# MAIN_TX.net
KiCad netlist of a schematic drawn in Altium Designer
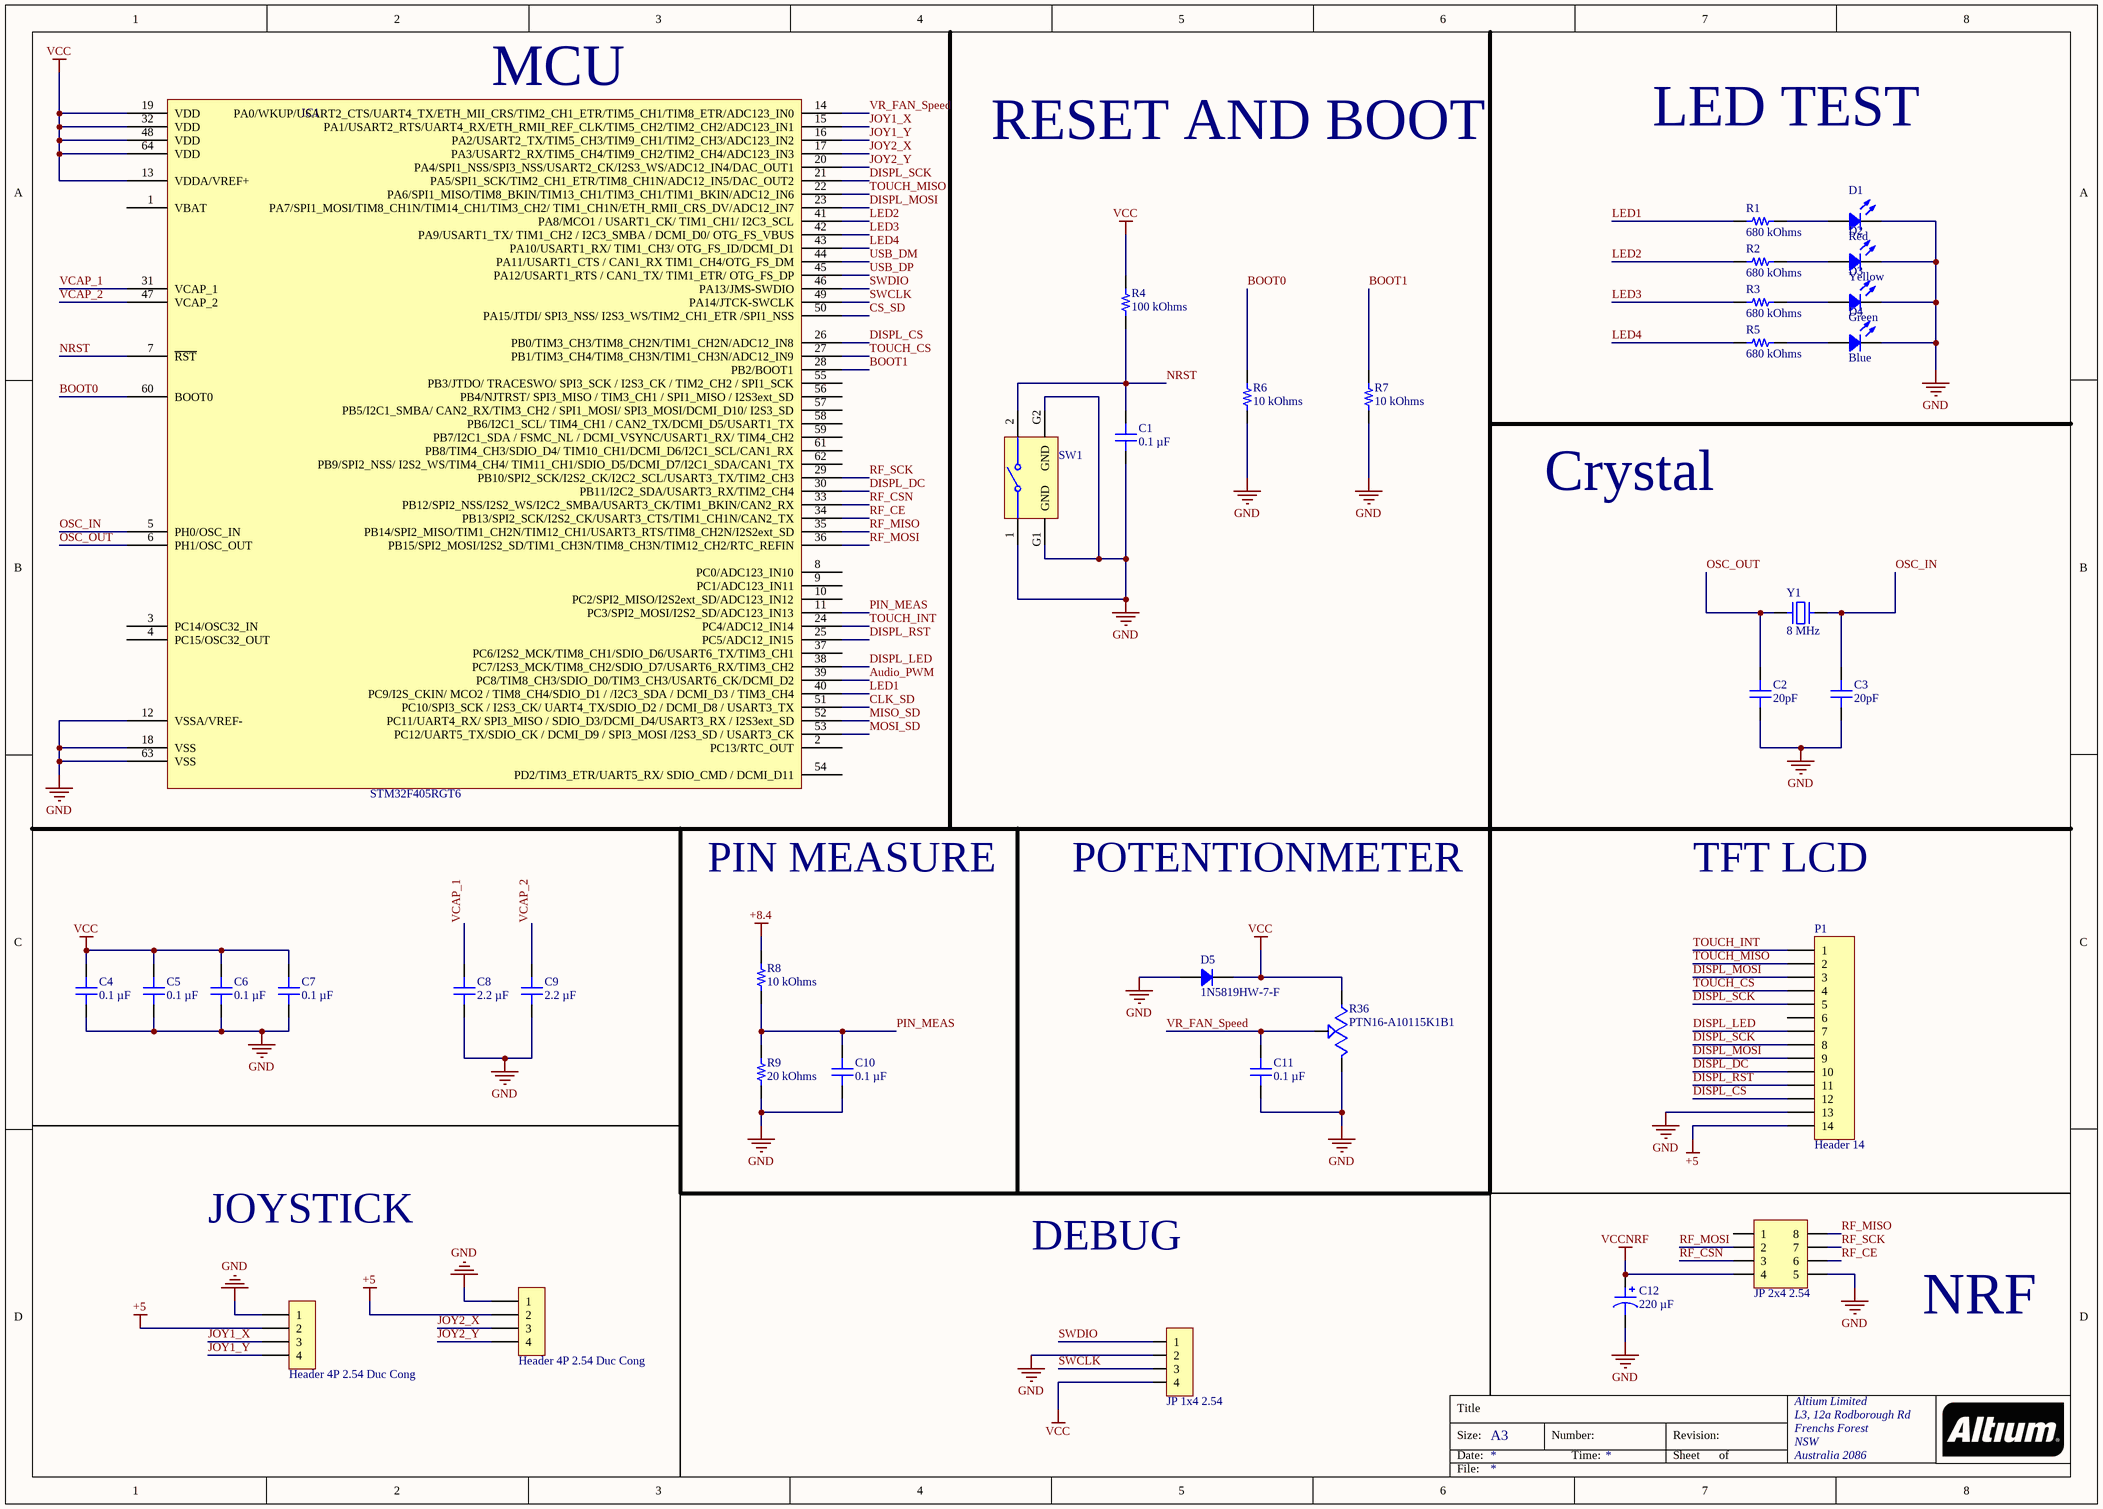
[diagram p0: MAIN_TX.SchDoc]

(export (version "E")
  (design (tool "Eeschema 10.0.6"))
  (components
    (comp (ref "C1")
      (value "0.1 µF")
      (footprint "CAP 0603_1608")
      (description "CAP CER 0.1UF 10V X7R 0603")
      (fields
        (field (name "PART NUMBER") "VJ0603Y104MXQCW1BC")
        (field (name "MANUFACTURER") "Vishay Vitramon")
      )
      (libsource (lib "Celestial Altium Library - altium_library") (part "Capacitor"))
    )
    (comp (ref "C2")
      (value "20pF")
      (footprint "CAP 0603_1608")
      (description "CAP CER 20PF 16V NP0 0603")
      (fields (field (name "PART NUMBER") "0603YA200JAT2A") (field (name "MANUFACTURER") "AVX Corporation"))
      (libsource (lib "Celestial Altium Library - altium_library") (part "Capacitor"))
    )
    (comp (ref "C3")
      (value "20pF")
      (footprint "CAP 0603_1608")
      (description "CAP CER 20PF 16V NP0 0603")
      (fields (field (name "PART NUMBER") "0603YA200JAT2A") (field (name "MANUFACTURER") "AVX Corporation"))
      (libsource (lib "Celestial Altium Library - altium_library") (part "Capacitor"))
    )
    (comp (ref "C4")
      (value "0.1 µF")
      (footprint "CAP 0603_1608")
      (description "CAP CER 0.1UF 10V X7R 0603")
      (fields
        (field (name "PART NUMBER") "VJ0603Y104MXQCW1BC")
        (field (name "MANUFACTURER") "Vishay Vitramon")
      )
      (libsource (lib "Celestial Altium Library - altium_library") (part "Capacitor"))
    )
    (comp (ref "C5")
      (value "0.1 µF")
      (footprint "CAP 0603_1608")
      (description "CAP CER 0.1UF 10V X7R 0603")
      (fields
        (field (name "PART NUMBER") "VJ0603Y104MXQCW1BC")
        (field (name "MANUFACTURER") "Vishay Vitramon")
      )
      (libsource (lib "Celestial Altium Library - altium_library") (part "Capacitor"))
    )
    (comp (ref "C6")
      (value "0.1 µF")
      (footprint "CAP 0603_1608")
      (description "CAP CER 0.1UF 10V X7R 0603")
      (fields
        (field (name "PART NUMBER") "VJ0603Y104MXQCW1BC")
        (field (name "MANUFACTURER") "Vishay Vitramon")
      )
      (libsource (lib "Celestial Altium Library - altium_library") (part "Capacitor"))
    )
    (comp (ref "C7")
      (value "0.1 µF")
      (footprint "CAP 0603_1608")
      (description "CAP CER 0.1UF 10V X7R 0603")
      (fields
        (field (name "PART NUMBER") "VJ0603Y104MXQCW1BC")
        (field (name "MANUFACTURER") "Vishay Vitramon")
      )
      (libsource (lib "Celestial Altium Library - altium_library") (part "Capacitor"))
    )
    (comp (ref "C8")
      (value "2.2 µF")
      (footprint "CAP 0603_1608")
      (description "CAP CER 2.2UF 10V X7R 0603")
      (fields (field (name "PART NUMBER") "LMK107B7225MA-TR") (field (name "MANUFACTURER") "Taiyo Yuden"))
      (libsource (lib "Celestial Altium Library - altium_library") (part "Capacitor"))
    )
    (comp (ref "C9")
      (value "2.2 µF")
      (footprint "CAP 0603_1608")
      (description "CAP CER 2.2UF 10V X7R 0603")
      (fields (field (name "PART NUMBER") "LMK107B7225MA-TR") (field (name "MANUFACTURER") "Taiyo Yuden"))
      (libsource (lib "Celestial Altium Library - altium_library") (part "Capacitor"))
    )
    (comp (ref "C10")
      (value "0.1 µF")
      (footprint "CAP 0603_1608")
      (description "CAP CER 0.1UF 10V X7R 0603")
      (fields
        (field (name "PART NUMBER") "VJ0603Y104KXQCW1BC")
        (field (name "MANUFACTURER") "Vishay Vitramon")
      )
      (libsource (lib "Celestial Altium Library - altium_library") (part "Capacitor"))
    )
    (comp (ref "C11")
      (value "0.1 µF")
      (footprint "CAP 0603_1608")
      (description "CAP CER 0.1UF 10V X7R 0603")
      (fields
        (field (name "PART NUMBER") "VJ0603Y104KXQCW1BC")
        (field (name "MANUFACTURER") "Vishay Vitramon")
      )
      (libsource (lib "Celestial Altium Library - altium_library") (part "Capacitor"))
    )
    (comp (ref "C12")
      (value "220 µF")
      (footprint "CAP ALSMD 6.6MM H6.1MM")
      (description "CAP ALUM 220UF 20% 10V SMD")
      (fields (field (name "PART NUMBER") "UCM1A221MCL1GS") (field (name "MANUFACTURER") "Nichicon"))
      (libsource (lib "Celestial Altium Library - altium_library") (part "Polarised Capacitor"))
    )
    (comp (ref "D1")
      (value "Red")
      (footprint "LED 0603_1608 RED")
      (description "LED RED 0603 SMD")
      (fields (field (name "PART NUMBER") "5973035507F") (field (name "MANUFACTURER") "Dialight"))
      (libsource (lib "Celestial Altium Library - altium_library") (part "LED"))
    )
    (comp (ref "D2")
      (value "Yellow")
      (footprint "LED 0603_1608 YELLOW")
      (description "LED YELLOW 0603 SMD")
      (fields (field (name "PART NUMBER") "SML-D13WWT86A") (field (name "MANUFACTURER") "Rohm Semiconductor"))
      (libsource (lib "Celestial Altium Library - altium_library") (part "LED"))
    )
    (comp (ref "D3")
      (value "Green")
      (footprint "LED 0603_1608 GREEN")
      (description "LED GREEN CLEAR 0603 SMD")
      (fields (field (name "PART NUMBER") "QBLP601-IG") (field (name "MANUFACTURER") "QT Brightek (QTB)"))
      (libsource (lib "Celestial Altium Library - altium_library") (part "LED"))
    )
    (comp (ref "D4")
      (value "Blue")
      (footprint "LED 0603_1608 BLUE")
      (description "LED BLUE CLEAR 0603 SMD")
      (fields
        (field (name "PART NUMBER") "VLMB1302-GS08")
        (field (name "MANUFACTURER") "Vishay Semiconductor Opto Division")
      )
      (libsource (lib "Celestial Altium Library - altium_library") (part "LED"))
    )
    (comp (ref "D5")
      (value "1N5819HW-7-F")
      (footprint "SOD-123")
      (description "DIODE SCHOTTKY 40V 1A SOD123")
      (fields (field (name "MANUFACTURER") "Diodes Incorporated"))
      (libsource (lib "Celestial Altium Library - altium_library") (part "Diode"))
    )
    (comp (ref "H2")
      (value "Header 4P 2.54 Duc Cong")
      (footprint "Header 4P DC 2.54")
      (description "Cắm")
      (libsource (lib "Header") (part "Header 4P 2.54 Duc Cong"))
    )
    (comp (ref "H3")
      (value "Header 4P 2.54 Duc Cong")
      (footprint "Header 4P DC 2.54")
      (description "Cắm")
      (libsource (lib "Header") (part "Header 4P 2.54 Duc Cong"))
    )
    (comp (ref "IC1")
      (value "STM32F405RGT6")
      (footprint "ST LQFP-64 10X10MM")
      (description "IC MCU 32BIT 1MB FLASH 64LQFP")
      (fields (field (name "MANUFACTURER") "STMicroelectronics"))
      (libsource (lib "Celestial Altium Library - altium_library") (part "ST STM32F405RGT6 64PIN"))
    )
    (comp (ref "JP1")
      (value "JP 2x4 2.54")
      (footprint "JP 2x4 CT")
      (description "Cắm")
      (libsource (lib "Jump") (part "JP 2x4 2.54 Cai Thang"))
    )
    (comp (ref "JP4")
      (value "JP 1x4 2.54")
      (footprint "JP 1x4 CC")
      (description "Cắm")
      (libsource (lib "Jump") (part "JP 1x4 2.54 Cai Cong"))
    )
    (comp (ref "P1")
      (value "Header 14")
      (footprint "HDR1X14")
      (description "Header, 14-Pin")
      (fields (field (name "PUBLISHER") "Altium Limited"))
      (libsource (lib "Library AL") (part "Header 14"))
    )
    (comp (ref "R1")
      (value "680 kOhms")
      (footprint "RES 0603_1608")
      (description "RES 680 KOHM 0.1% 1/16W 0603")
      (fields (field (name "PART NUMBER") "RGT1608P-684-B-T5") (field (name "MANUFACTURER") "Susumu"))
      (libsource (lib "Celestial Altium Library - altium_library") (part "Resistor"))
    )
    (comp (ref "R2")
      (value "680 kOhms")
      (footprint "RES 0603_1608")
      (description "RES 680 KOHM 0.1% 1/16W 0603")
      (fields (field (name "PART NUMBER") "RGT1608P-684-B-T5") (field (name "MANUFACTURER") "Susumu"))
      (libsource (lib "Celestial Altium Library - altium_library") (part "Resistor"))
    )
    (comp (ref "R3")
      (value "680 kOhms")
      (footprint "RES 0603_1608")
      (description "RES 680 KOHM 0.1% 1/16W 0603")
      (fields (field (name "PART NUMBER") "RGT1608P-684-B-T5") (field (name "MANUFACTURER") "Susumu"))
      (libsource (lib "Celestial Altium Library - altium_library") (part "Resistor"))
    )
    (comp (ref "R4")
      (value "100 kOhms")
      (footprint "RES 0603_1608")
      (description "RES SMD 100K OHM 0.1% 1/10W 0603")
      (fields
        (field (name "PART NUMBER") "MCT06030E1003BP100")
        (field (name "MANUFACTURER") "Vishay Beyschlag")
      )
      (libsource (lib "Celestial Altium Library - altium_library") (part "Resistor"))
    )
    (comp (ref "R5")
      (value "680 kOhms")
      (footprint "RES 0603_1608")
      (description "RES 680 KOHM 0.1% 1/16W 0603")
      (fields (field (name "PART NUMBER") "RGT1608P-684-B-T5") (field (name "MANUFACTURER") "Susumu"))
      (libsource (lib "Celestial Altium Library - altium_library") (part "Resistor"))
    )
    (comp (ref "R6")
      (value "10 kOhms")
      (footprint "RES 0603_1608")
      (description "RES SMD 10K OHM 0.5% 0.15W 0603")
      (fields
        (field (name "PART NUMBER") "MCT0603MD1002DP500")
        (field (name "MANUFACTURER") "Vishay Beyschlag")
      )
      (libsource (lib "Celestial Altium Library - altium_library") (part "Resistor"))
    )
    (comp (ref "R7")
      (value "10 kOhms")
      (footprint "RES 0603_1608")
      (description "RES SMD 10K OHM 0.5% 0.15W 0603")
      (fields
        (field (name "PART NUMBER") "MCT0603MD1002DP500")
        (field (name "MANUFACTURER") "Vishay Beyschlag")
      )
      (libsource (lib "Celestial Altium Library - altium_library") (part "Resistor"))
    )
    (comp (ref "R8")
      (value "10 kOhms")
      (footprint "RES 0603_1608")
      (description "RES SMD 10K OHM 0.5% 0.15W 0603")
      (fields
        (field (name "PART NUMBER") "MCT0603MD1002DP500")
        (field (name "MANUFACTURER") "Vishay Beyschlag")
      )
      (libsource (lib "Celestial Altium Library - altium_library") (part "Resistor"))
    )
    (comp (ref "R9")
      (value "20 kOhms")
      (footprint "RES 0603_1608")
      (description "RES SMD 20K OHM 0.1% 1/10W 0603")
      (fields (field (name "PART NUMBER") "RG1608P-203-B-T5") (field (name "MANUFACTURER") "Susumu"))
      (libsource (lib "Celestial Altium Library - altium_library") (part "Resistor"))
    )
    (comp (ref "R36")
      (value "PTN16-A10115K1B1")
      (footprint "POT_PTN16-A10115K1B1")
      (fields (field (name "MF") "{'manufacturer': u'CUI Devices'}"))
      (libsource (lib "PTN16-A10115K1B1") (part "PTN16-A10115K1B1"))
    )
    (comp (ref "SW1")
      (value "431256083716")
      (footprint "4312560837x6")
      (description "WS-TATU THT Tact Switch 6x6mm Right Angled Type with ground terminal, SPST-NO, 12VDC, 50mA, 160g")
      (fields (field (name "MANUFACTURER") "Wurth Elektronik"))
      (libsource (lib "Altium_WS-TATU_rev22a") (part "431256083716"))
    )
    (comp (ref "Y1")
      (value "8 MHz")
      (footprint "NDK NX5032GA")
      (description "CRYSTAL 8.0000MHZ 8PF SMD")
      (fields
        (field (name "PART NUMBER") "NX5032GA-8.000M-STD-CSU-1")
        (field (name "MANUFACTURER") "NDK America, Inc.")
      )
      (libsource (lib "Celestial Altium Library - altium_library") (part "NDK Crystal NX5032GA"))
    )
  )
  (nets
    (net (code "1") (name "+5") (class "Default")
      (node (ref "H2") (pin "2") (pinfunction "2_2") (pintype "passive"))
      (node (ref "H3") (pin "2") (pinfunction "2_2") (pintype "passive"))
      (node (ref "P1") (pin "14") (pinfunction "14_14") (pintype "passive"))
    )
    (net (code "2") (name "+8.4") (class "Default")
      (node (ref "R8") (pin "2") (pinfunction "2_2") (pintype "passive"))
    )
    (net (code "3") (name "/Audio_PWM") (class "Default")
      (node (ref "IC1") (pin "39") (pinfunction "PC8/TIM8_CH3/SDIO_D0/TIM3_CH3/USART6_CK/DCMI_D2_39") (pintype "passive"))
    )
    (net (code "4") (name "/BOOT0") (class "Default")
      (node (ref "IC1") (pin "60") (pinfunction "BOOT0_60") (pintype "passive"))
      (node (ref "R6") (pin "2") (pinfunction "2_2") (pintype "passive"))
    )
    (net (code "5") (name "/BOOT1") (class "Default")
      (node (ref "IC1") (pin "28") (pinfunction "PB2/BOOT1_28") (pintype "passive"))
      (node (ref "R7") (pin "2") (pinfunction "2_2") (pintype "passive"))
    )
    (net (code "6") (name "/CLK_SD") (class "Default")
      (node (ref "IC1") (pin "51") (pinfunction "PC10/SPI3_SCK_/_I2S3_CK/_UART4_TX/SDIO_D2_/_DCMI_D8_/_USART3_TX_51") (pintype "passive"))
    )
    (net (code "7") (name "/CS_SD") (class "Default")
      (node (ref "IC1") (pin "50") (pinfunction "PA15/JTDI/_SPI3_NSS/_I2S3_WS/TIM2_CH1_ETR_/SPI1_NSS_50") (pintype "passive"))
    )
    (net (code "8") (name "/DISPL_CS") (class "Default")
      (node (ref "IC1") (pin "26") (pinfunction "PB0/TIM3_CH3/TIM8_CH2N/TIM1_CH2N/ADC12_IN8_26") (pintype "passive"))
      (node (ref "P1") (pin "12") (pinfunction "12_12") (pintype "passive"))
    )
    (net (code "9") (name "/DISPL_DC") (class "Default")
      (node (ref "IC1") (pin "30") (pinfunction "PB11/I2C2_SDA/USART3_RX/TIM2_CH4_30") (pintype "passive"))
      (node (ref "P1") (pin "10") (pinfunction "10_10") (pintype "passive"))
    )
    (net (code "10") (name "/DISPL_LED") (class "Default")
      (node (ref "IC1") (pin "38") (pinfunction "PC7/I2S3_MCK/TIM8_CH2/SDIO_D7/USART6_RX/TIM3_CH2_38") (pintype "passive"))
      (node (ref "P1") (pin "7") (pinfunction "7_7") (pintype "passive"))
    )
    (net (code "11") (name "/DISPL_MOSI") (class "Default")
      (node (ref "IC1") (pin "23") (pinfunction "PA7/SPI1_MOSI/TIM8_CH1N/TIM14_CH1/TIM3_CH2/_TIM1_CH1N/ETH_RMII_CRS_DV/ADC12_IN7_23") (pintype "passive"))
      (node (ref "P1") (pin "3") (pinfunction "3_3") (pintype "passive"))
      (node (ref "P1") (pin "9") (pinfunction "9_9") (pintype "passive"))
    )
    (net (code "12") (name "/DISPL_RST") (class "Default")
      (node (ref "IC1") (pin "25") (pinfunction "PC5/ADC12_IN15_25") (pintype "passive"))
      (node (ref "P1") (pin "11") (pinfunction "11_11") (pintype "passive"))
    )
    (net (code "13") (name "/DISPL_SCK") (class "Default")
      (node (ref "IC1") (pin "21") (pinfunction "PA5/SPI1_SCK/TIM2_CH1_ETR/TIM8_CH1N/ADC12_IN5/DAC_OUT2_21") (pintype "passive"))
      (node (ref "P1") (pin "5") (pinfunction "5_5") (pintype "passive"))
      (node (ref "P1") (pin "8") (pinfunction "8_8") (pintype "passive"))
    )
    (net (code "14") (name "/JOY1_X") (class "Default")
      (node (ref "H3") (pin "3") (pinfunction "3_3") (pintype "passive"))
      (node (ref "IC1") (pin "15") (pinfunction "PA1/USART2_RTS/UART4_RX/ETH_RMII_REF_CLK/TIM5_CH2/TIM2_CH2/ADC123_IN1_15") (pintype "passive"))
    )
    (net (code "15") (name "/JOY1_Y") (class "Default")
      (node (ref "H3") (pin "4") (pinfunction "4_4") (pintype "passive"))
      (node (ref "IC1") (pin "16") (pinfunction "PA2/USART2_TX/TIM5_CH3/TIM9_CH1/TIM2_CH3/ADC123_IN2_16") (pintype "passive"))
    )
    (net (code "16") (name "/JOY2_X") (class "Default")
      (node (ref "H2") (pin "3") (pinfunction "3_3") (pintype "passive"))
      (node (ref "IC1") (pin "17") (pinfunction "PA3/USART2_RX/TIM5_CH4/TIM9_CH2/TIM2_CH4/ADC123_IN3_17") (pintype "passive"))
    )
    (net (code "17") (name "/JOY2_Y") (class "Default")
      (node (ref "H2") (pin "4") (pinfunction "4_4") (pintype "passive"))
      (node (ref "IC1") (pin "20") (pinfunction "PA4/SPI1_NSS/SPI3_NSS/USART2_CK/I2S3_WS/ADC12_IN4/DAC_OUT1_20") (pintype "passive"))
    )
    (net (code "18") (name "/LED1") (class "Default")
      (node (ref "IC1") (pin "40") (pinfunction "PC9/I2S_CKIN/_MCO2_/_TIM8_CH4/SDIO_D1_/_/I2C3_SDA_/_DCMI_D3_/_TIM3_CH4_40") (pintype "passive"))
      (node (ref "R1") (pin "1") (pinfunction "1_1") (pintype "passive"))
    )
    (net (code "19") (name "/LED2") (class "Default")
      (node (ref "IC1") (pin "41") (pinfunction "PA8/MCO1_/_USART1_CK/_TIM1_CH1/_I2C3_SCL_41") (pintype "passive"))
      (node (ref "R2") (pin "1") (pinfunction "1_1") (pintype "passive"))
    )
    (net (code "20") (name "/LED3") (class "Default")
      (node (ref "IC1") (pin "42") (pinfunction "PA9/USART1_TX/_TIM1_CH2_/_I2C3_SMBA_/_DCMI_D0/_OTG_FS_VBUS_42") (pintype "passive"))
      (node (ref "R3") (pin "1") (pinfunction "1_1") (pintype "passive"))
    )
    (net (code "21") (name "/LED4") (class "Default")
      (node (ref "IC1") (pin "43") (pinfunction "PA10/USART1_RX/_TIM1_CH3/_OTG_FS_ID/DCMI_D1_43") (pintype "passive"))
      (node (ref "R5") (pin "1") (pinfunction "1_1") (pintype "passive"))
    )
    (net (code "22") (name "/MISO_SD") (class "Default")
      (node (ref "IC1") (pin "52") (pinfunction "PC11/UART4_RX/_SPI3_MISO_/_SDIO_D3/DCMI_D4/USART3_RX_/_I2S3ext_SD_52") (pintype "passive"))
    )
    (net (code "23") (name "/MOSI_SD") (class "Default")
      (node (ref "IC1") (pin "53") (pinfunction "PC12/UART5_TX/SDIO_CK_/_DCMI_D9_/_SPI3_MOSI_/I2S3_SD_/_USART3_CK_53") (pintype "passive"))
    )
    (net (code "24") (name "/NRST") (class "Default")
      (node (ref "C1") (pin "2") (pinfunction "2_2") (pintype "passive"))
      (node (ref "IC1") (pin "7") (pinfunction "~{RST}_7") (pintype "passive"))
      (node (ref "R4") (pin "1") (pinfunction "1_1") (pintype "passive"))
      (node (ref "SW1") (pin "2") (pinfunction "2_2") (pintype "passive"))
    )
    (net (code "25") (name "/OSC_IN") (class "Default")
      (node (ref "C3") (pin "2") (pinfunction "2_2") (pintype "passive"))
      (node (ref "IC1") (pin "5") (pinfunction "PH0/OSC_IN_5") (pintype "passive"))
      (node (ref "Y1") (pin "2") (pinfunction "2_2") (pintype "passive"))
    )
    (net (code "26") (name "/OSC_OUT") (class "Default")
      (node (ref "C2") (pin "2") (pinfunction "2_2") (pintype "passive"))
      (node (ref "IC1") (pin "6") (pinfunction "PH1/OSC_OUT_6") (pintype "passive"))
      (node (ref "Y1") (pin "1") (pinfunction "1_1") (pintype "passive"))
    )
    (net (code "27") (name "/PIN_MEAS") (class "Default")
      (node (ref "C10") (pin "2") (pinfunction "2_2") (pintype "passive"))
      (node (ref "IC1") (pin "11") (pinfunction "PC3/SPI2_MOSI/I2S2_SD/ADC123_IN13_11") (pintype "passive"))
      (node (ref "R8") (pin "1") (pinfunction "1_1") (pintype "passive"))
      (node (ref "R9") (pin "2") (pinfunction "2_2") (pintype "passive"))
    )
    (net (code "28") (name "/RF_CE") (class "Default")
      (node (ref "IC1") (pin "34") (pinfunction "PB13/SPI2_SCK/I2S2_CK/USART3_CTS/TIM1_CH1N/CAN2_TX_34") (pintype "passive"))
      (node (ref "JP1") (pin "6") (pinfunction "6_6") (pintype "passive"))
    )
    (net (code "29") (name "/RF_CSN") (class "Default")
      (node (ref "IC1") (pin "33") (pinfunction "PB12/SPI2_NSS/I2S2_WS/I2C2_SMBA/USART3_CK/TIM1_BKIN/CAN2_RX_33") (pintype "passive"))
      (node (ref "JP1") (pin "3") (pinfunction "3_3") (pintype "passive"))
    )
    (net (code "30") (name "/RF_MISO") (class "Default")
      (node (ref "IC1") (pin "35") (pinfunction "PB14/SPI2_MISO/TIM1_CH2N/TIM12_CH1/USART3_RTS/TIM8_CH2N/I2S2ext_SD_35") (pintype "passive"))
      (node (ref "JP1") (pin "8") (pinfunction "8_8") (pintype "passive"))
    )
    (net (code "31") (name "/RF_MOSI") (class "Default")
      (node (ref "IC1") (pin "36") (pinfunction "PB15/SPI2_MOSI/I2S2_SD/TIM1_CH3N/TIM8_CH3N/TIM12_CH2/RTC_REFIN_36") (pintype "passive"))
      (node (ref "JP1") (pin "2") (pinfunction "2_2") (pintype "passive"))
    )
    (net (code "32") (name "/RF_SCK") (class "Default")
      (node (ref "IC1") (pin "29") (pinfunction "PB10/SPI2_SCK/I2S2_CK/I2C2_SCL/USART3_TX/TIM2_CH3_29") (pintype "passive"))
      (node (ref "JP1") (pin "7") (pinfunction "7_7") (pintype "passive"))
    )
    (net (code "33") (name "/SWCLK") (class "Default")
      (node (ref "IC1") (pin "49") (pinfunction "PA14/JTCK-SWCLK_49") (pintype "passive"))
      (node (ref "JP4") (pin "3") (pinfunction "3_3") (pintype "passive"))
    )
    (net (code "34") (name "/SWDIO") (class "Default")
      (node (ref "IC1") (pin "46") (pinfunction "PA13/JMS-SWDIO_46") (pintype "passive"))
      (node (ref "JP4") (pin "1") (pinfunction "1_1") (pintype "passive"))
    )
    (net (code "35") (name "/TOUCH_CS") (class "Default")
      (node (ref "IC1") (pin "27") (pinfunction "PB1/TIM3_CH4/TIM8_CH3N/TIM1_CH3N/ADC12_IN9_27") (pintype "passive"))
      (node (ref "P1") (pin "4") (pinfunction "4_4") (pintype "passive"))
    )
    (net (code "36") (name "/TOUCH_INT") (class "Default")
      (node (ref "IC1") (pin "24") (pinfunction "PC4/ADC12_IN14_24") (pintype "passive"))
      (node (ref "P1") (pin "1") (pinfunction "1_1") (pintype "passive"))
    )
    (net (code "37") (name "/TOUCH_MISO") (class "Default")
      (node (ref "IC1") (pin "22") (pinfunction "PA6/SPI1_MISO/TIM8_BKIN/TIM13_CH1/TIM3_CH1/TIM1_BKIN/ADC12_IN6_22") (pintype "passive"))
      (node (ref "P1") (pin "2") (pinfunction "2_2") (pintype "passive"))
    )
    (net (code "38") (name "/USB_DM") (class "Default")
      (node (ref "IC1") (pin "44") (pinfunction "PA11/USART1_CTS_/_CAN1_RX_TIM1_CH4/OTG_FS_DM_44") (pintype "passive"))
    )
    (net (code "39") (name "/USB_DP") (class "Default")
      (node (ref "IC1") (pin "45") (pinfunction "PA12/USART1_RTS_/_CAN1_TX/_TIM1_ETR/_OTG_FS_DP_45") (pintype "passive"))
    )
    (net (code "40") (name "/VCAP_1") (class "Default")
      (node (ref "C8") (pin "2") (pinfunction "2_2") (pintype "passive"))
      (node (ref "IC1") (pin "31") (pinfunction "VCAP_1_31") (pintype "passive"))
    )
    (net (code "41") (name "/VCAP_2") (class "Default")
      (node (ref "C9") (pin "2") (pinfunction "2_2") (pintype "passive"))
      (node (ref "IC1") (pin "47") (pinfunction "VCAP_2_47") (pintype "passive"))
    )
    (net (code "42") (name "/VR_FAN_Speed") (class "Default")
      (node (ref "C11") (pin "2") (pinfunction "2_2") (pintype "passive"))
      (node (ref "IC1") (pin "14") (pinfunction "PA0/WKUP/USART2_CTS/UART4_TX/ETH_MII_CRS/TIM2_CH1_ETR/TIM5_CH1/TIM8_ETR/ADC123_IN0_14") (pintype "passive"))
      (node (ref "R36") (pin "2") (pinfunction "2_2") (pintype "passive"))
    )
    (net (code "43") (name "GND") (class "Default")
      (node (ref "C1") (pin "1") (pinfunction "1_1") (pintype "passive"))
      (node (ref "C10") (pin "1") (pinfunction "1_1") (pintype "passive"))
      (node (ref "C11") (pin "1") (pinfunction "1_1") (pintype "passive"))
      (node (ref "C12") (pin "2") (pinfunction "2_2") (pintype "passive"))
      (node (ref "C2") (pin "1") (pinfunction "1_1") (pintype "passive"))
      (node (ref "C3") (pin "1") (pinfunction "1_1") (pintype "passive"))
      (node (ref "C4") (pin "1") (pinfunction "1_1") (pintype "passive"))
      (node (ref "C5") (pin "1") (pinfunction "1_1") (pintype "passive"))
      (node (ref "C6") (pin "1") (pinfunction "1_1") (pintype "passive"))
      (node (ref "C7") (pin "1") (pinfunction "1_1") (pintype "passive"))
      (node (ref "C8") (pin "1") (pinfunction "1_1") (pintype "passive"))
      (node (ref "C9") (pin "1") (pinfunction "1_1") (pintype "passive"))
      (node (ref "D1") (pin "2") (pinfunction "2_2") (pintype "passive"))
      (node (ref "D2") (pin "2") (pinfunction "2_2") (pintype "passive"))
      (node (ref "D3") (pin "2") (pinfunction "2_2") (pintype "passive"))
      (node (ref "D4") (pin "2") (pinfunction "2_2") (pintype "passive"))
      (node (ref "D5") (pin "1") (pinfunction "1_1") (pintype "passive"))
      (node (ref "H2") (pin "1") (pinfunction "1_1") (pintype "passive"))
      (node (ref "H3") (pin "1") (pinfunction "1_1") (pintype "passive"))
      (node (ref "IC1") (pin "12") (pinfunction "VSSA/VREF-_12") (pintype "passive"))
      (node (ref "IC1") (pin "18") (pinfunction "VSS_18") (pintype "passive"))
      (node (ref "IC1") (pin "63") (pinfunction "VSS_63") (pintype "passive"))
      (node (ref "JP1") (pin "5") (pinfunction "5_5") (pintype "passive"))
      (node (ref "JP4") (pin "2") (pinfunction "2_2") (pintype "passive"))
      (node (ref "P1") (pin "13") (pinfunction "13_13") (pintype "passive"))
      (node (ref "R36") (pin "3") (pinfunction "3_3") (pintype "passive"))
      (node (ref "R6") (pin "1") (pinfunction "1_1") (pintype "passive"))
      (node (ref "R7") (pin "1") (pinfunction "1_1") (pintype "passive"))
      (node (ref "R9") (pin "1") (pinfunction "1_1") (pintype "passive"))
      (node (ref "SW1") (pin "1") (pinfunction "1_1") (pintype "passive"))
      (node (ref "SW1") (pin "G1") (pinfunction "GND_G1") (pintype "passive"))
      (node (ref "SW1") (pin "G2") (pinfunction "GND_G2") (pintype "passive"))
    )
    (net (code "44") (name "Net-(D1-Pad1)") (class "Default")
      (node (ref "D1") (pin "1") (pinfunction "1_1") (pintype "passive"))
      (node (ref "R1") (pin "2") (pinfunction "2_2") (pintype "passive"))
    )
    (net (code "45") (name "Net-(D2-Pad1)") (class "Default")
      (node (ref "D2") (pin "1") (pinfunction "1_1") (pintype "passive"))
      (node (ref "R2") (pin "2") (pinfunction "2_2") (pintype "passive"))
    )
    (net (code "46") (name "Net-(D3-Pad1)") (class "Default")
      (node (ref "D3") (pin "1") (pinfunction "1_1") (pintype "passive"))
      (node (ref "R3") (pin "2") (pinfunction "2_2") (pintype "passive"))
    )
    (net (code "47") (name "Net-(D4-Pad1)") (class "Default")
      (node (ref "D4") (pin "1") (pinfunction "1_1") (pintype "passive"))
      (node (ref "R5") (pin "2") (pinfunction "2_2") (pintype "passive"))
    )
    (net (code "48") (name "VCC") (class "Default")
      (node (ref "C4") (pin "2") (pinfunction "2_2") (pintype "passive"))
      (node (ref "C5") (pin "2") (pinfunction "2_2") (pintype "passive"))
      (node (ref "C6") (pin "2") (pinfunction "2_2") (pintype "passive"))
      (node (ref "C7") (pin "2") (pinfunction "2_2") (pintype "passive"))
      (node (ref "D5") (pin "2") (pinfunction "2_2") (pintype "passive"))
      (node (ref "IC1") (pin "13") (pinfunction "VDDA/VREF+_13") (pintype "passive"))
      (node (ref "IC1") (pin "19") (pinfunction "VDD_19") (pintype "passive"))
      (node (ref "IC1") (pin "32") (pinfunction "VDD_32") (pintype "passive"))
      (node (ref "IC1") (pin "48") (pinfunction "VDD_48") (pintype "passive"))
      (node (ref "IC1") (pin "64") (pinfunction "VDD_64") (pintype "passive"))
      (node (ref "JP4") (pin "4") (pinfunction "4_4") (pintype "passive"))
      (node (ref "R36") (pin "1") (pinfunction "1_1") (pintype "passive"))
      (node (ref "R4") (pin "2") (pinfunction "2_2") (pintype "passive"))
    )
    (net (code "49") (name "VCCNRF") (class "Default")
      (node (ref "C12") (pin "1") (pinfunction "1_1") (pintype "passive"))
      (node (ref "JP1") (pin "4") (pinfunction "4_4") (pintype "passive"))
    )
    (net (code "50") (name "unconnected-(IC1-PB3{slash}JTDO{slash}_TRACESWO{slash}_SPI3_SCK_{slash}_I2S3_CK_{slash}_TIM2_CH2_{slash}_SPI1_SCK-Pad55)") (class "Default")
      (node (ref "IC1") (pin "55") (pinfunction "PB3/JTDO/_TRACESWO/_SPI3_SCK_/_I2S3_CK_/_TIM2_CH2_/_SPI1_SCK_55") (pintype "passive"))
    )
    (net (code "51") (name "unconnected-(IC1-PB4{slash}NJTRST{slash}_SPI3_MISO_{slash}_TIM3_CH1_{slash}_SPI1_MISO_{slash}_I2S3ext_SD-Pad56)") (class "Default")
      (node (ref "IC1") (pin "56") (pinfunction "PB4/NJTRST/_SPI3_MISO_/_TIM3_CH1_/_SPI1_MISO_/_I2S3ext_SD_56") (pintype "passive"))
    )
    (net (code "52") (name "unconnected-(IC1-PB5{slash}I2C1_SMBA{slash}_CAN2_RX{slash}TIM3_CH2_{slash}_SPI1_MOSI{slash}_SPI3_MOSI{slash}DCMI_D10{slash}_I2S3_SD-Pad57)") (class "Default")
      (node (ref "IC1") (pin "57") (pinfunction "PB5/I2C1_SMBA/_CAN2_RX/TIM3_CH2_/_SPI1_MOSI/_SPI3_MOSI/DCMI_D10/_I2S3_SD_57") (pintype "passive"))
    )
    (net (code "53") (name "unconnected-(IC1-PB6{slash}I2C1_SCL{slash}_TIM4_CH1_{slash}_CAN2_TX{slash}DCMI_D5{slash}USART1_TX-Pad58)") (class "Default")
      (node (ref "IC1") (pin "58") (pinfunction "PB6/I2C1_SCL/_TIM4_CH1_/_CAN2_TX/DCMI_D5/USART1_TX_58") (pintype "passive"))
    )
    (net (code "54") (name "unconnected-(IC1-PB7{slash}I2C1_SDA_{slash}_FSMC_NL_{slash}_DCMI_VSYNC{slash}USART1_RX{slash}_TIM4_CH2-Pad59)") (class "Default")
      (node (ref "IC1") (pin "59") (pinfunction "PB7/I2C1_SDA_/_FSMC_NL_/_DCMI_VSYNC/USART1_RX/_TIM4_CH2_59") (pintype "passive"))
    )
    (net (code "55") (name "unconnected-(IC1-PB8{slash}TIM4_CH3{slash}SDIO_D4{slash}_TIM10_CH1{slash}DCMI_D6{slash}I2C1_SCL{slash}CAN1_RX-Pad61)") (class "Default")
      (node (ref "IC1") (pin "61") (pinfunction "PB8/TIM4_CH3/SDIO_D4/_TIM10_CH1/DCMI_D6/I2C1_SCL/CAN1_RX_61") (pintype "passive"))
    )
    (net (code "56") (name "unconnected-(IC1-PB9{slash}SPI2_NSS{slash}_I2S2_WS{slash}TIM4_CH4{slash}_TIM11_CH1{slash}SDIO_D5{slash}DCMI_D7{slash}I2C1_SDA{slash}CAN1_TX-Pad62)") (class "Default")
      (node (ref "IC1") (pin "62") (pinfunction "PB9/SPI2_NSS/_I2S2_WS/TIM4_CH4/_TIM11_CH1/SDIO_D5/DCMI_D7/I2C1_SDA/CAN1_TX_62") (pintype "passive"))
    )
    (net (code "57") (name "unconnected-(IC1-PC0{slash}ADC123_IN10-Pad8)") (class "Default")
      (node (ref "IC1") (pin "8") (pinfunction "PC0/ADC123_IN10_8") (pintype "passive"))
    )
    (net (code "58") (name "unconnected-(IC1-PC1{slash}ADC123_IN11-Pad9)") (class "Default")
      (node (ref "IC1") (pin "9") (pinfunction "PC1/ADC123_IN11_9") (pintype "passive"))
    )
    (net (code "59") (name "unconnected-(IC1-PC2{slash}SPI2_MISO{slash}I2S2ext_SD{slash}ADC123_IN12-Pad10)") (class "Default")
      (node (ref "IC1") (pin "10") (pinfunction "PC2/SPI2_MISO/I2S2ext_SD/ADC123_IN12_10") (pintype "passive"))
    )
    (net (code "60") (name "unconnected-(IC1-PC6{slash}I2S2_MCK{slash}TIM8_CH1{slash}SDIO_D6{slash}USART6_TX{slash}TIM3_CH1-Pad37)") (class "Default")
      (node (ref "IC1") (pin "37") (pinfunction "PC6/I2S2_MCK/TIM8_CH1/SDIO_D6/USART6_TX/TIM3_CH1_37") (pintype "passive"))
    )
    (net (code "61") (name "unconnected-(IC1-PC13{slash}RTC_OUT-Pad2)") (class "Default")
      (node (ref "IC1") (pin "2") (pinfunction "PC13/RTC_OUT_2") (pintype "passive"))
    )
    (net (code "62") (name "unconnected-(IC1-PC14{slash}OSC32_IN-Pad3)") (class "Default")
      (node (ref "IC1") (pin "3") (pinfunction "PC14/OSC32_IN_3") (pintype "passive"))
    )
    (net (code "63") (name "unconnected-(IC1-PC15{slash}OSC32_OUT-Pad4)") (class "Default")
      (node (ref "IC1") (pin "4") (pinfunction "PC15/OSC32_OUT_4") (pintype "passive"))
    )
    (net (code "64") (name "unconnected-(IC1-PD2{slash}TIM3_ETR{slash}UART5_RX{slash}_SDIO_CMD_{slash}_DCMI_D11-Pad54)") (class "Default")
      (node (ref "IC1") (pin "54") (pinfunction "PD2/TIM3_ETR/UART5_RX/_SDIO_CMD_/_DCMI_D11_54") (pintype "passive"))
    )
    (net (code "65") (name "unconnected-(IC1-VBAT-Pad1)") (class "Default")
      (node (ref "IC1") (pin "1") (pinfunction "VBAT_1") (pintype "passive"))
    )
    (net (code "66") (name "unconnected-(JP1-Pad1)") (class "Default")
      (node (ref "JP1") (pin "1") (pinfunction "1_1") (pintype "passive"))
    )
    (net (code "67") (name "unconnected-(P1-Pad6)") (class "Default")
      (node (ref "P1") (pin "6") (pinfunction "6_6") (pintype "passive"))
    )
  )
)
